# SonicVisualizer.net
KiCad netlist of a schematic drawn in EAGLE
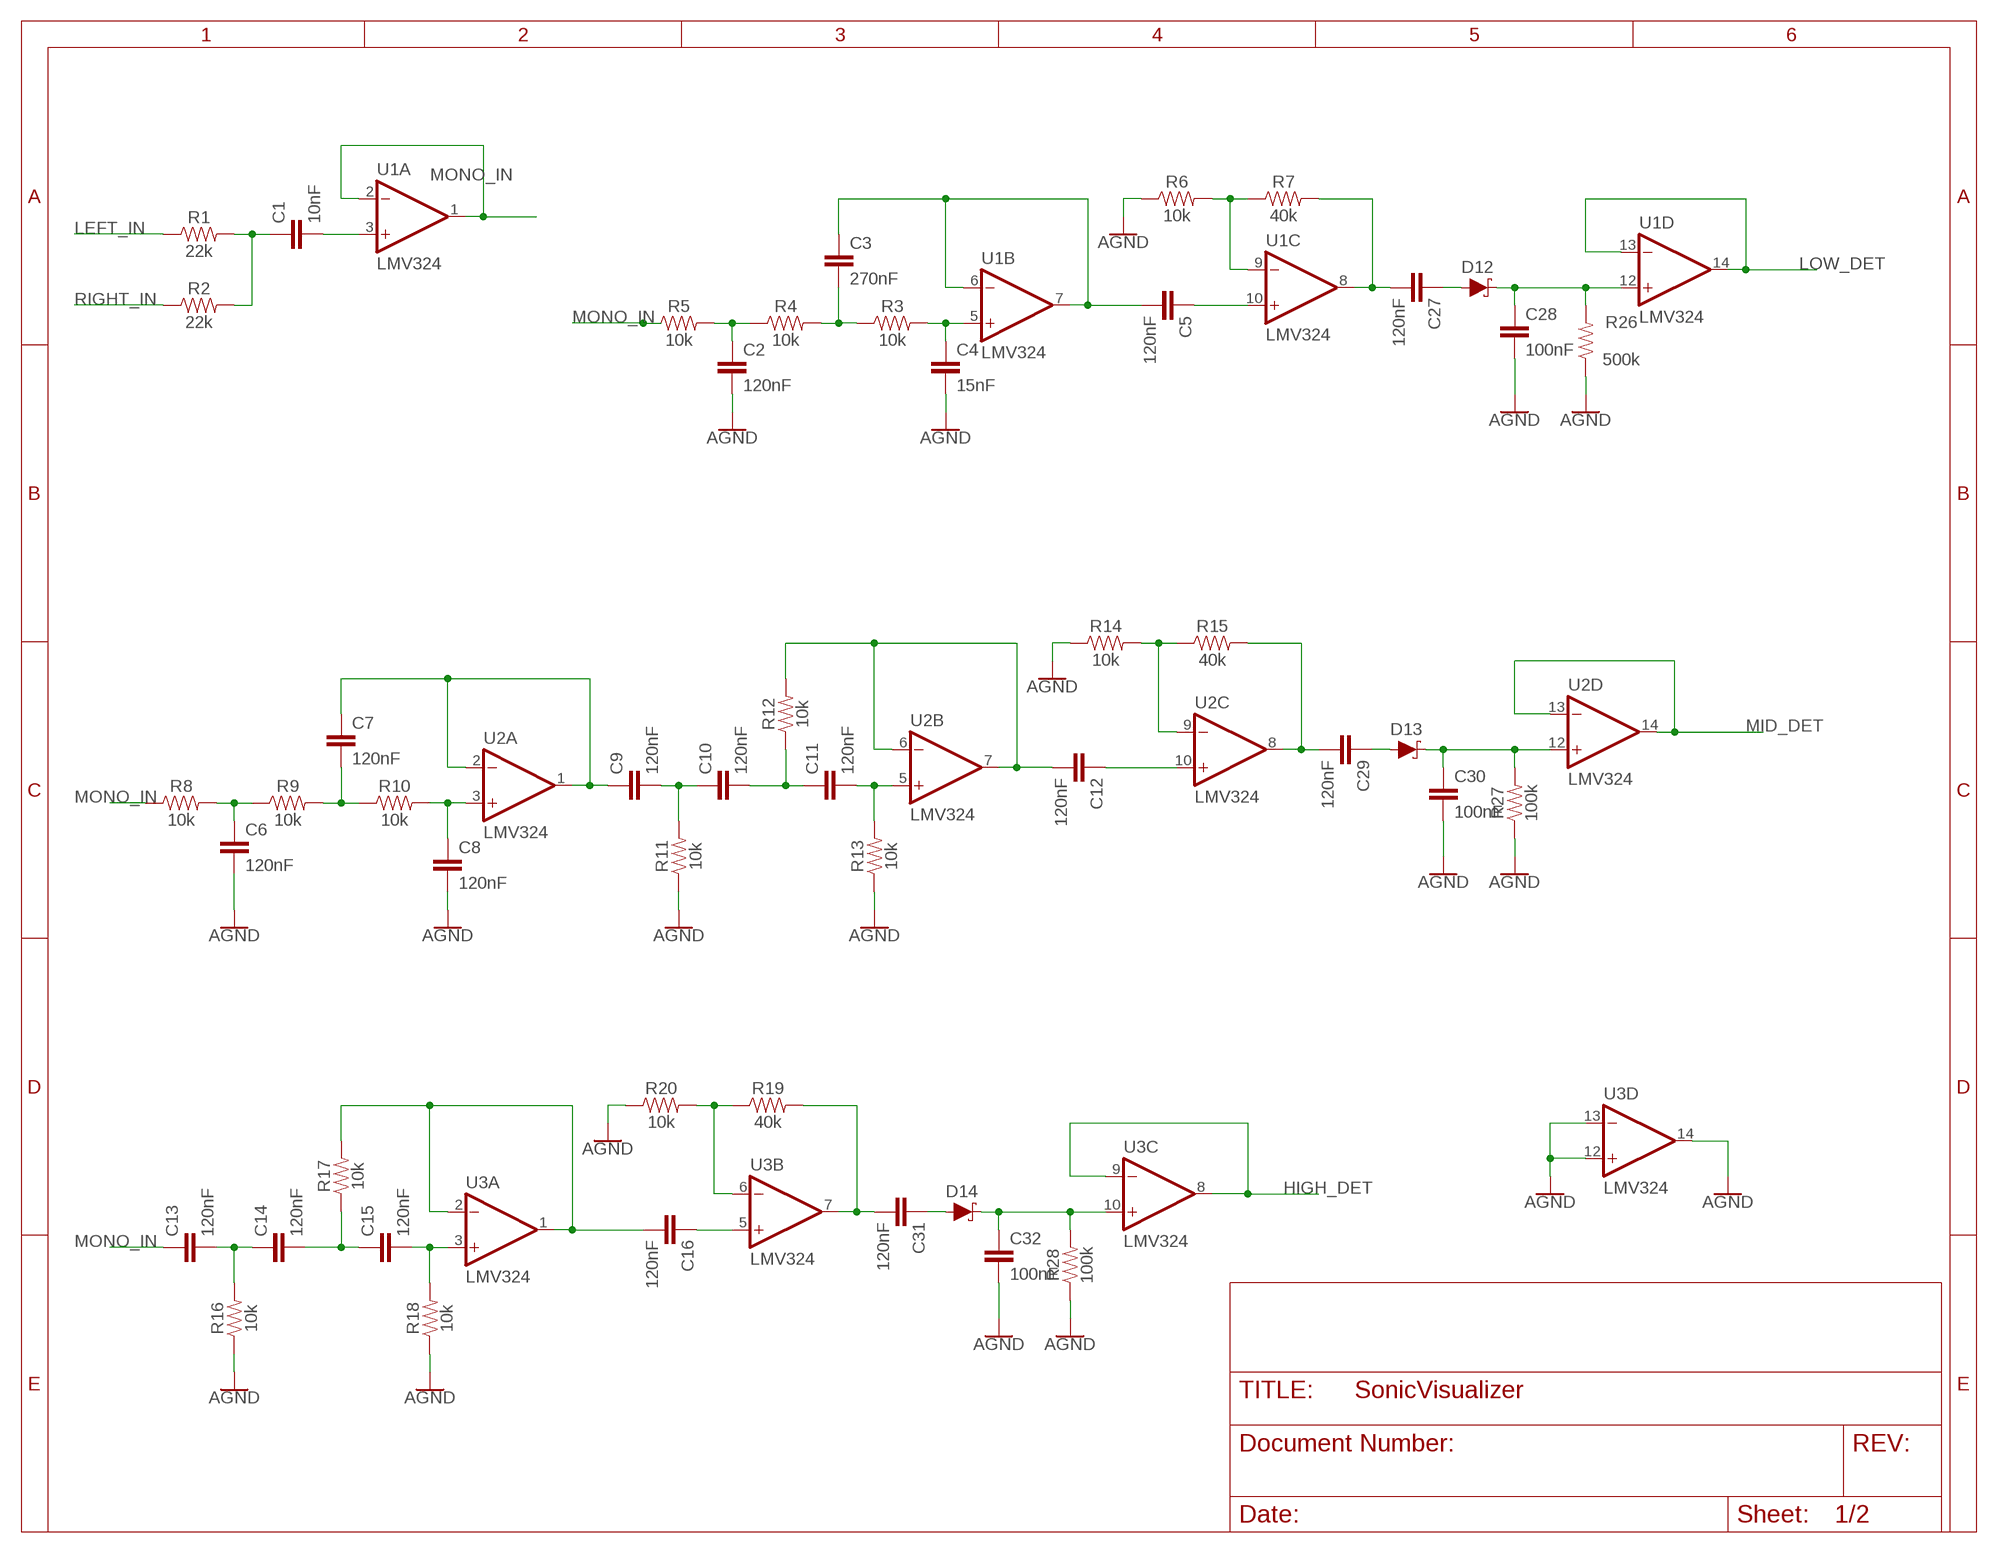
[diagram p0: schematic, sheet 1]
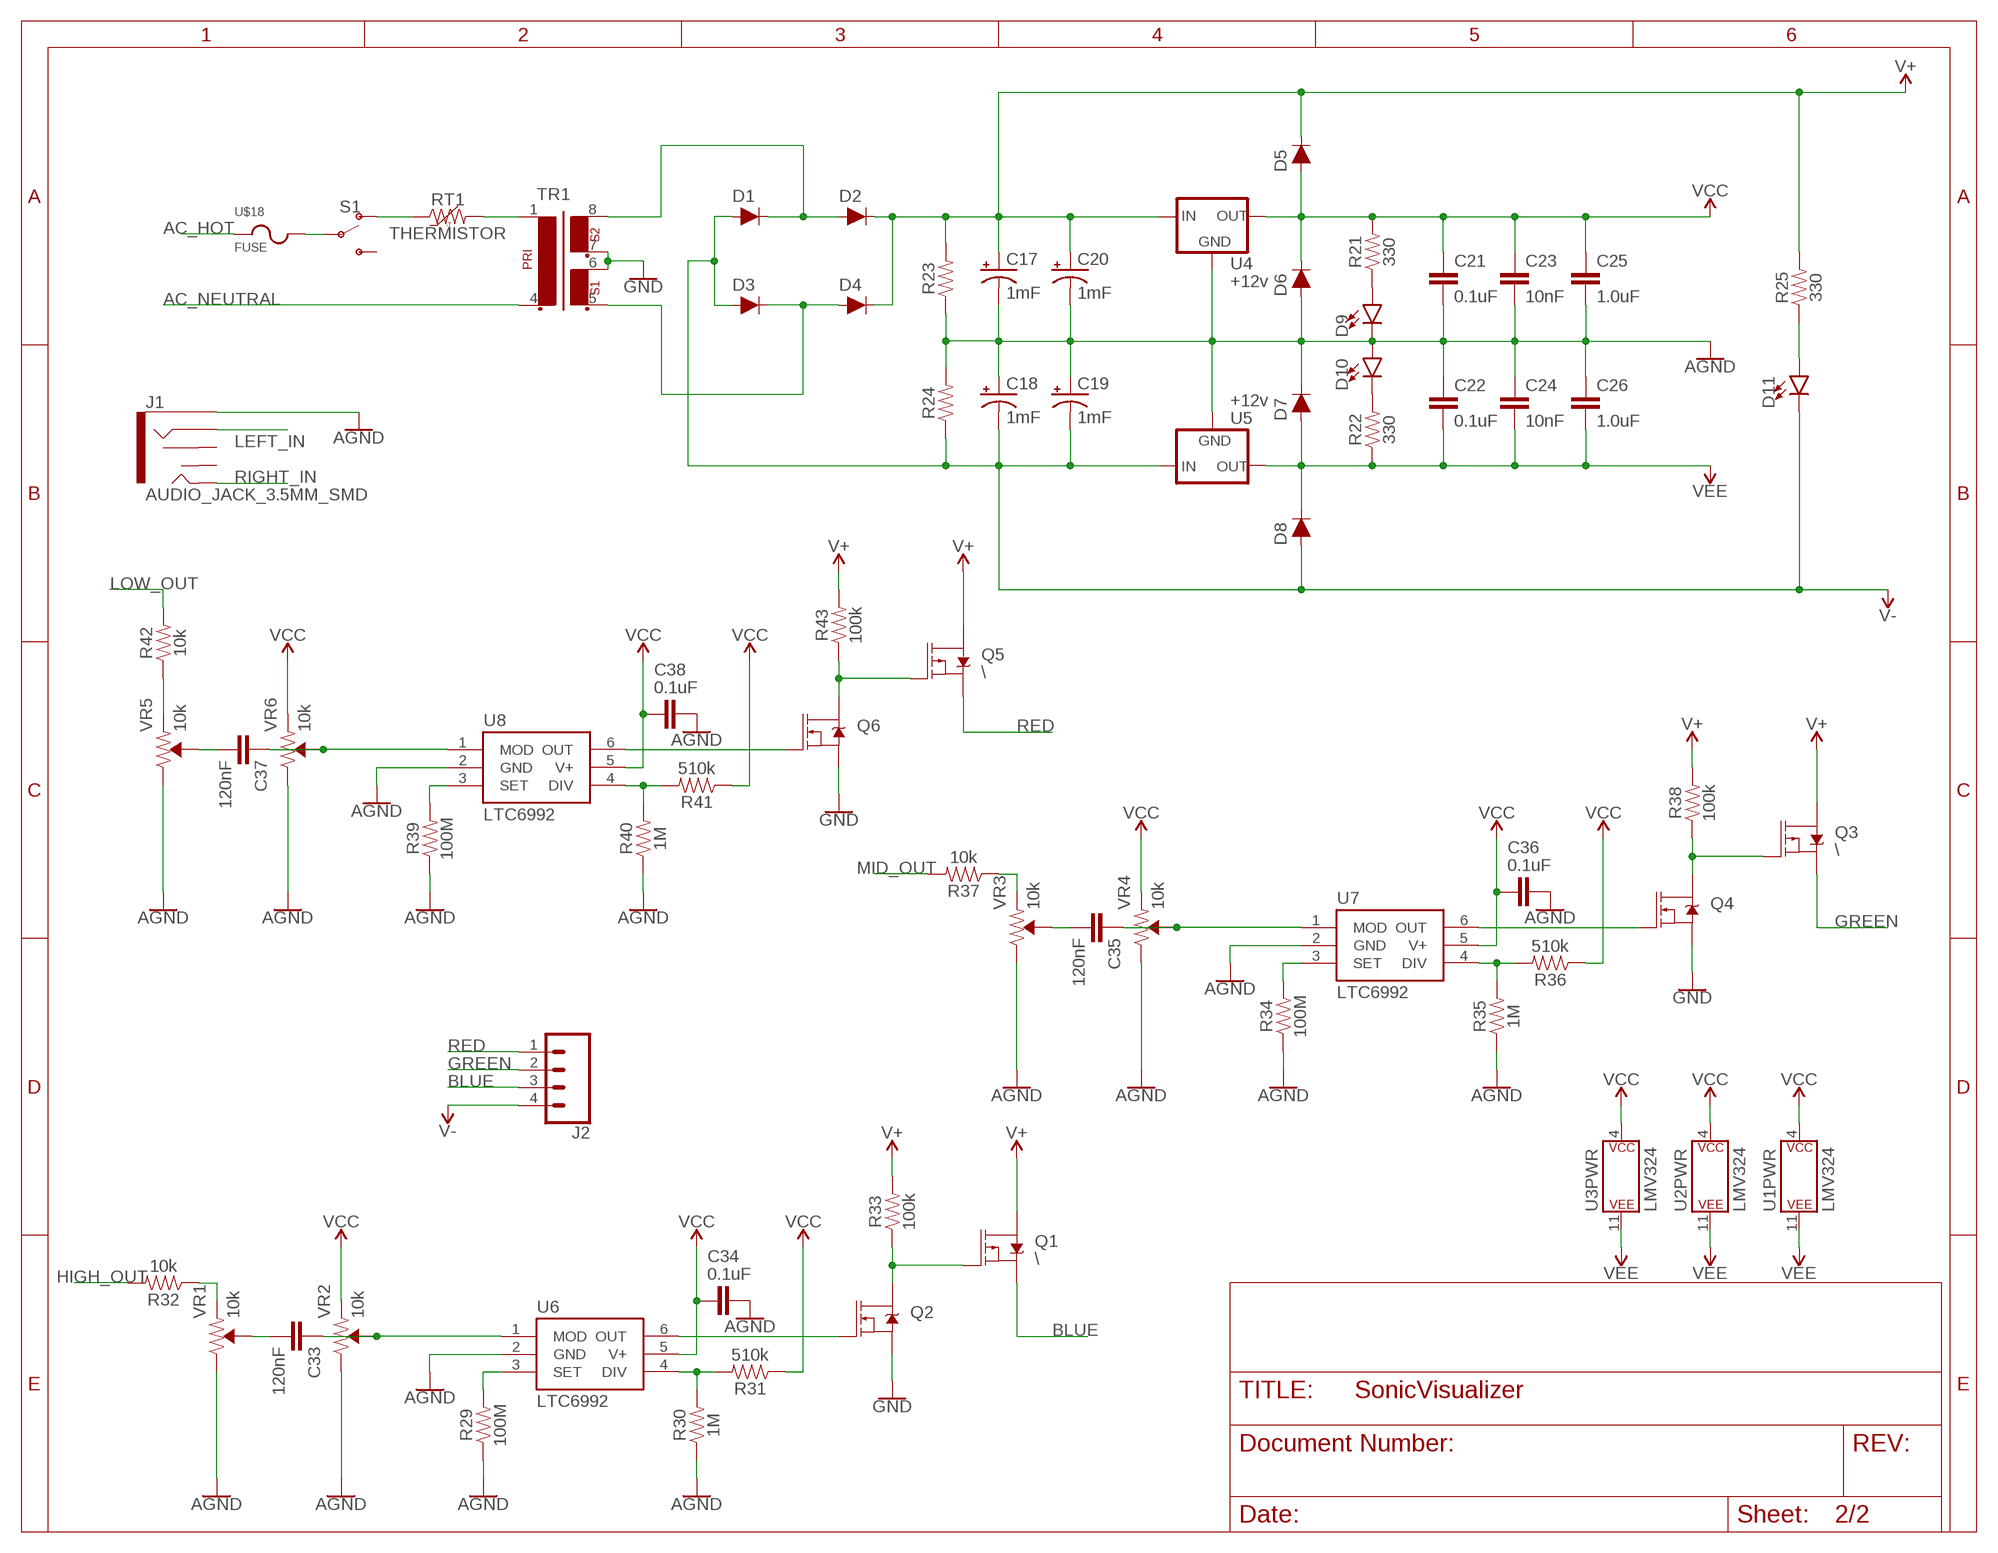
[diagram p1: schematic, sheet 2]

(export (version "E")
  (design (tool "Eeschema 10.0.6"))
  (components
    (comp (ref "C1")
      (value "10nF")
      (footprint "eagle-import:0603")
      (libsource (lib "eagle-import") (part "10NF-0603-50V-10%"))
    )
    (comp (ref "C2")
      (value "120nF")
      (footprint "eagle-import:0603")
      (libsource (lib "eagle-import") (part "0.1UF-0603-25V-(+80/-20%)"))
    )
    (comp (ref "C3")
      (value "270nF")
      (footprint "eagle-import:0603")
      (libsource (lib "eagle-import") (part "0.1UF-0603-25V-(+80/-20%)"))
    )
    (comp (ref "C4")
      (value "15nF")
      (footprint "eagle-import:0603")
      (libsource (lib "eagle-import") (part "0.1UF-0603-25V-(+80/-20%)"))
    )
    (comp (ref "C5")
      (value "120nF")
      (footprint "eagle-import:0603")
      (libsource (lib "eagle-import") (part "0.1UF-0603-25V-(+80/-20%)"))
    )
    (comp (ref "C6")
      (value "120nF")
      (footprint "eagle-import:0603")
      (libsource (lib "eagle-import") (part "0.1UF-0603-25V-(+80/-20%)"))
    )
    (comp (ref "C7")
      (value "120nF")
      (footprint "eagle-import:0603")
      (libsource (lib "eagle-import") (part "0.1UF-0603-25V-(+80/-20%)"))
    )
    (comp (ref "C8")
      (value "120nF")
      (footprint "eagle-import:0603")
      (libsource (lib "eagle-import") (part "0.1UF-0603-25V-(+80/-20%)"))
    )
    (comp (ref "C9")
      (value "120nF")
      (footprint "eagle-import:0603")
      (libsource (lib "eagle-import") (part "0.1UF-0603-25V-(+80/-20%)"))
    )
    (comp (ref "C10")
      (value "120nF")
      (footprint "eagle-import:0603")
      (libsource (lib "eagle-import") (part "0.1UF-0603-25V-(+80/-20%)"))
    )
    (comp (ref "C11")
      (value "120nF")
      (footprint "eagle-import:0603")
      (libsource (lib "eagle-import") (part "0.1UF-0603-25V-(+80/-20%)"))
    )
    (comp (ref "C12")
      (value "120nF")
      (footprint "eagle-import:0603")
      (libsource (lib "eagle-import") (part "0.1UF-0603-25V-(+80/-20%)"))
    )
    (comp (ref "C13")
      (value "120nF")
      (footprint "eagle-import:0603")
      (libsource (lib "eagle-import") (part "0.1UF-0603-25V-(+80/-20%)"))
    )
    (comp (ref "C14")
      (value "120nF")
      (footprint "eagle-import:0603")
      (libsource (lib "eagle-import") (part "0.1UF-0603-25V-(+80/-20%)"))
    )
    (comp (ref "C15")
      (value "120nF")
      (footprint "eagle-import:0603")
      (libsource (lib "eagle-import") (part "0.1UF-0603-25V-(+80/-20%)"))
    )
    (comp (ref "C16")
      (value "120nF")
      (footprint "eagle-import:0603")
      (libsource (lib "eagle-import") (part "0.1UF-0603-25V-(+80/-20%)"))
    )
    (comp (ref "C27")
      (value "120nF")
      (footprint "eagle-import:0603")
      (libsource (lib "eagle-import") (part "0.1UF-0603-25V-(+80/-20%)"))
    )
    (comp (ref "C28")
      (value "100nF")
      (footprint "eagle-import:0603")
      (libsource (lib "eagle-import") (part "0.1UF-0603-25V-(+80/-20%)"))
    )
    (comp (ref "C29")
      (value "120nF")
      (footprint "eagle-import:0603")
      (libsource (lib "eagle-import") (part "0.1UF-0603-25V-(+80/-20%)"))
    )
    (comp (ref "C30")
      (value "100nF")
      (footprint "eagle-import:0603")
      (libsource (lib "eagle-import") (part "0.1UF-0603-25V-(+80/-20%)"))
    )
    (comp (ref "C31")
      (value "120nF")
      (footprint "eagle-import:0603")
      (libsource (lib "eagle-import") (part "0.1UF-0603-25V-(+80/-20%)"))
    )
    (comp (ref "C32")
      (value "100nF")
      (footprint "eagle-import:0603")
      (libsource (lib "eagle-import") (part "0.1UF-0603-25V-(+80/-20%)"))
    )
    (comp (ref "D12")
      (value "DIODE-SCHOTTKY-SS14")
      (footprint "eagle-import:SMA-DIODE")
      (libsource (lib "eagle-import") (part "DIODE-SCHOTTKY-SS14"))
    )
    (comp (ref "D13")
      (value "DIODE-SCHOTTKY-SS14")
      (footprint "eagle-import:SMA-DIODE")
      (libsource (lib "eagle-import") (part "DIODE-SCHOTTKY-SS14"))
    )
    (comp (ref "D14")
      (value "DIODE-SCHOTTKY-SS14")
      (footprint "eagle-import:SMA-DIODE")
      (libsource (lib "eagle-import") (part "DIODE-SCHOTTKY-SS14"))
    )
    (comp (ref "R1")
      (value "22k")
      (footprint "eagle-import:0603")
      (libsource (lib "eagle-import") (part "22KOHM-0603-1/10W-1%"))
    )
    (comp (ref "R2")
      (value "22k")
      (footprint "eagle-import:0603")
      (libsource (lib "eagle-import") (part "22KOHM-0603-1/10W-1%"))
    )
    (comp (ref "R3")
      (value "10k")
      (footprint "eagle-import:0603")
      (libsource (lib "eagle-import") (part "10KOHM-0603-1/10W-1%"))
    )
    (comp (ref "R4")
      (value "10k")
      (footprint "eagle-import:0603")
      (libsource (lib "eagle-import") (part "10KOHM-0603-1/10W-1%"))
    )
    (comp (ref "R5")
      (value "10k")
      (footprint "eagle-import:0603")
      (libsource (lib "eagle-import") (part "10KOHM-0603-1/10W-1%"))
    )
    (comp (ref "R6")
      (value "10k")
      (footprint "eagle-import:0603")
      (libsource (lib "eagle-import") (part "10KOHM-0603-1/10W-1%"))
    )
    (comp (ref "R7")
      (value "40k")
      (footprint "eagle-import:0603")
      (libsource (lib "eagle-import") (part "10KOHM-0603-1/10W-1%"))
    )
    (comp (ref "R8")
      (value "10k")
      (footprint "eagle-import:0603")
      (libsource (lib "eagle-import") (part "10KOHM-0603-1/10W-1%"))
    )
    (comp (ref "R9")
      (value "10k")
      (footprint "eagle-import:0603")
      (libsource (lib "eagle-import") (part "10KOHM-0603-1/10W-1%"))
    )
    (comp (ref "R10")
      (value "10k")
      (footprint "eagle-import:0603")
      (libsource (lib "eagle-import") (part "10KOHM-0603-1/10W-1%"))
    )
    (comp (ref "R11")
      (value "10k")
      (footprint "eagle-import:0603")
      (libsource (lib "eagle-import") (part "10KOHM-0603-1/10W-1%"))
    )
    (comp (ref "R12")
      (value "10k")
      (footprint "eagle-import:0603")
      (libsource (lib "eagle-import") (part "10KOHM-0603-1/10W-1%"))
    )
    (comp (ref "R13")
      (value "10k")
      (footprint "eagle-import:0603")
      (libsource (lib "eagle-import") (part "10KOHM-0603-1/10W-1%"))
    )
    (comp (ref "R14")
      (value "10k")
      (footprint "eagle-import:0603")
      (libsource (lib "eagle-import") (part "10KOHM-0603-1/10W-1%"))
    )
    (comp (ref "R15")
      (value "40k")
      (footprint "eagle-import:0603")
      (libsource (lib "eagle-import") (part "10KOHM-0603-1/10W-1%"))
    )
    (comp (ref "R16")
      (value "10k")
      (footprint "eagle-import:0603")
      (libsource (lib "eagle-import") (part "10KOHM-0603-1/10W-1%"))
    )
    (comp (ref "R17")
      (value "10k")
      (footprint "eagle-import:0603")
      (libsource (lib "eagle-import") (part "10KOHM-0603-1/10W-1%"))
    )
    (comp (ref "R18")
      (value "10k")
      (footprint "eagle-import:0603")
      (libsource (lib "eagle-import") (part "10KOHM-0603-1/10W-1%"))
    )
    (comp (ref "R19")
      (value "40k")
      (footprint "eagle-import:0603")
      (libsource (lib "eagle-import") (part "10KOHM-0603-1/10W-1%"))
    )
    (comp (ref "R20")
      (value "10k")
      (footprint "eagle-import:0603")
      (libsource (lib "eagle-import") (part "10KOHM-0603-1/10W-1%"))
    )
    (comp (ref "R26")
      (value "500k")
      (footprint "eagle-import:0603")
      (libsource (lib "eagle-import") (part "10KOHM-0603-1/10W-1%"))
    )
    (comp (ref "R27")
      (value "100k")
      (footprint "eagle-import:0603")
      (libsource (lib "eagle-import") (part "10KOHM-0603-1/10W-1%"))
    )
    (comp (ref "R28")
      (value "100k")
      (footprint "eagle-import:0603")
      (libsource (lib "eagle-import") (part "10KOHM-0603-1/10W-1%"))
    )
    (comp (ref "U1")
      (value "LMV324")
      (footprint "eagle-import:SO14")
      (libsource (lib "eagle-import") (part "LMV324"))
    )
    (comp (ref "U2")
      (value "LMV324")
      (footprint "eagle-import:SO14")
      (libsource (lib "eagle-import") (part "LMV324"))
    )
    (comp (ref "U3")
      (value "LMV324")
      (footprint "eagle-import:SO14")
      (libsource (lib "eagle-import") (part "LMV324"))
    )
    (comp (ref "C17")
      (value "1mF")
      (footprint "eagle-import:CPOL-RADIAL-5MM-10MM")
      (libsource (lib "eagle-import") (part "1000UF-RADIAL-5MM-25V-20%"))
    )
    (comp (ref "C18")
      (value "1mF")
      (footprint "eagle-import:CPOL-RADIAL-5MM-10MM")
      (libsource (lib "eagle-import") (part "1000UF-RADIAL-5MM-25V-20%"))
    )
    (comp (ref "C19")
      (value "1mF")
      (footprint "eagle-import:CPOL-RADIAL-5MM-10MM")
      (libsource (lib "eagle-import") (part "1000UF-RADIAL-5MM-25V-20%"))
    )
    (comp (ref "C20")
      (value "1mF")
      (footprint "eagle-import:CPOL-RADIAL-5MM-10MM")
      (libsource (lib "eagle-import") (part "1000UF-RADIAL-5MM-25V-20%"))
    )
    (comp (ref "C21")
      (value "0.1uF")
      (footprint "eagle-import:0603")
      (libsource (lib "eagle-import") (part "0.1UF-0603-25V-(+80/-20%)"))
    )
    (comp (ref "C22")
      (value "0.1uF")
      (footprint "eagle-import:0603")
      (libsource (lib "eagle-import") (part "0.1UF-0603-25V-(+80/-20%)"))
    )
    (comp (ref "C23")
      (value "10nF")
      (footprint "eagle-import:0603")
      (libsource (lib "eagle-import") (part "10NF-0603-50V-10%"))
    )
    (comp (ref "C24")
      (value "10nF")
      (footprint "eagle-import:0603")
      (libsource (lib "eagle-import") (part "10NF-0603-50V-10%"))
    )
    (comp (ref "C25")
      (value "1.0uF")
      (footprint "eagle-import:0603")
      (libsource (lib "eagle-import") (part "1.0UF-0603-16V-10%"))
    )
    (comp (ref "C26")
      (value "1.0uF")
      (footprint "eagle-import:0603")
      (libsource (lib "eagle-import") (part "1.0UF-0603-16V-10%"))
    )
    (comp (ref "C33")
      (value "120nF")
      (footprint "eagle-import:0603")
      (libsource (lib "eagle-import") (part "0.1UF-0603-25V-(+80/-20%)"))
    )
    (comp (ref "C34")
      (value "0.1uF")
      (footprint "eagle-import:0603")
      (libsource (lib "eagle-import") (part "0.1UF-0603-25V-(+80/-20%)"))
    )
    (comp (ref "C35")
      (value "120nF")
      (footprint "eagle-import:0603")
      (libsource (lib "eagle-import") (part "0.1UF-0603-25V-(+80/-20%)"))
    )
    (comp (ref "C36")
      (value "0.1uF")
      (footprint "eagle-import:0603")
      (libsource (lib "eagle-import") (part "0.1UF-0603-25V-(+80/-20%)"))
    )
    (comp (ref "C37")
      (value "120nF")
      (footprint "eagle-import:0603")
      (libsource (lib "eagle-import") (part "0.1UF-0603-25V-(+80/-20%)"))
    )
    (comp (ref "C38")
      (value "0.1uF")
      (footprint "eagle-import:0603")
      (libsource (lib "eagle-import") (part "0.1UF-0603-25V-(+80/-20%)"))
    )
    (comp (ref "D1")
      (value "DIODE-PTH")
      (footprint "eagle-import:DIODE-1N4001")
      (libsource (lib "eagle-import") (part "DIODE-PTH"))
    )
    (comp (ref "D2")
      (value "DIODE-PTH")
      (footprint "eagle-import:DIODE-1N4001")
      (libsource (lib "eagle-import") (part "DIODE-PTH"))
    )
    (comp (ref "D3")
      (value "DIODE-PTH")
      (footprint "eagle-import:DIODE-1N4001")
      (libsource (lib "eagle-import") (part "DIODE-PTH"))
    )
    (comp (ref "D4")
      (value "DIODE-PTH")
      (footprint "eagle-import:DIODE-1N4001")
      (libsource (lib "eagle-import") (part "DIODE-PTH"))
    )
    (comp (ref "D5")
      (value "DIODE-PTH")
      (footprint "eagle-import:DIODE-1N4001")
      (libsource (lib "eagle-import") (part "DIODE-PTH"))
    )
    (comp (ref "D6")
      (value "DIODE-PTH")
      (footprint "eagle-import:DIODE-1N4001")
      (libsource (lib "eagle-import") (part "DIODE-PTH"))
    )
    (comp (ref "D7")
      (value "DIODE-PTH")
      (footprint "eagle-import:DIODE-1N4001")
      (libsource (lib "eagle-import") (part "DIODE-PTH"))
    )
    (comp (ref "D8")
      (value "DIODE-PTH")
      (footprint "eagle-import:DIODE-1N4001")
      (libsource (lib "eagle-import") (part "DIODE-PTH"))
    )
    (comp (ref "D9")
      (value "LED0603")
      (footprint "eagle-import:LED-0603")
      (libsource (lib "eagle-import") (part "LED0603"))
    )
    (comp (ref "D10")
      (value "LED0603")
      (footprint "eagle-import:LED-0603")
      (libsource (lib "eagle-import") (part "LED0603"))
    )
    (comp (ref "D11")
      (value "LED0603")
      (footprint "eagle-import:LED-0603")
      (libsource (lib "eagle-import") (part "LED0603"))
    )
    (comp (ref "J1")
      (value "AUDIO_JACK_3.5MM_SMD")
      (footprint "eagle-import:AUDIO-JACK-3.5MM-SMD")
      (libsource (lib "eagle-import") (part "AUDIO_JACK_3.5MM_SMD"))
    )
    (comp (ref "J2")
      (value "CONN_04")
      (footprint "eagle-import:1X04")
      (libsource (lib "eagle-import") (part "CONN_04"))
    )
    (comp (ref "Q1")
      (value "\\")
      (footprint "eagle-import:SOT23-3")
      (libsource (lib "eagle-import") (part "MOSFET_PCH-IRLML2244"))
    )
    (comp (ref "Q2")
      (value "MOSFET-NCH-2N7002PW")
      (footprint "eagle-import:SOT323")
      (libsource (lib "eagle-import") (part "MOSFET-NCH-2N7002PW"))
    )
    (comp (ref "Q3")
      (value "\\")
      (footprint "eagle-import:SOT23-3")
      (libsource (lib "eagle-import") (part "MOSFET_PCH-IRLML2244"))
    )
    (comp (ref "Q4")
      (value "MOSFET-NCH-2N7002PW")
      (footprint "eagle-import:SOT323")
      (libsource (lib "eagle-import") (part "MOSFET-NCH-2N7002PW"))
    )
    (comp (ref "Q5")
      (value "\\")
      (footprint "eagle-import:SOT23-3")
      (libsource (lib "eagle-import") (part "MOSFET_PCH-IRLML2244"))
    )
    (comp (ref "Q6")
      (value "MOSFET-NCH-2N7002PW")
      (footprint "eagle-import:SOT323")
      (libsource (lib "eagle-import") (part "MOSFET-NCH-2N7002PW"))
    )
    (comp (ref "R21")
      (value "330")
      (footprint "eagle-import:0603")
      (libsource (lib "eagle-import") (part "330OHM-0603-1/10W-1%"))
    )
    (comp (ref "R22")
      (value "330")
      (footprint "eagle-import:0603")
      (libsource (lib "eagle-import") (part "330OHM-0603-1/10W-1%"))
    )
    (comp (ref "R23")
      (value "RESISTORAXIAL-0.3")
      (footprint "eagle-import:AXIAL-0.3")
      (libsource (lib "eagle-import") (part "RESISTORAXIAL-0.3"))
    )
    (comp (ref "R24")
      (value "RESISTORAXIAL-0.3")
      (footprint "eagle-import:AXIAL-0.3")
      (libsource (lib "eagle-import") (part "RESISTORAXIAL-0.3"))
    )
    (comp (ref "R25")
      (value "330")
      (footprint "eagle-import:0603")
      (libsource (lib "eagle-import") (part "330OHM-0603-1/10W-1%"))
    )
    (comp (ref "R29")
      (value "100M")
      (footprint "eagle-import:0603")
      (libsource (lib "eagle-import") (part "10KOHM-0603-1/10W-1%"))
    )
    (comp (ref "R30")
      (value "1M")
      (footprint "eagle-import:0603")
      (libsource (lib "eagle-import") (part "10KOHM-0603-1/10W-1%"))
    )
    (comp (ref "R31")
      (value "510k")
      (footprint "eagle-import:0603")
      (libsource (lib "eagle-import") (part "10KOHM-0603-1/10W-1%"))
    )
    (comp (ref "R32")
      (value "10k")
      (footprint "eagle-import:0603")
      (libsource (lib "eagle-import") (part "10KOHM-0603-1/10W-1%"))
    )
    (comp (ref "R33")
      (value "100k")
      (footprint "eagle-import:0603")
      (libsource (lib "eagle-import") (part "10KOHM-0603-1/10W-1%"))
    )
    (comp (ref "R34")
      (value "100M")
      (footprint "eagle-import:0603")
      (libsource (lib "eagle-import") (part "10KOHM-0603-1/10W-1%"))
    )
    (comp (ref "R35")
      (value "1M")
      (footprint "eagle-import:0603")
      (libsource (lib "eagle-import") (part "10KOHM-0603-1/10W-1%"))
    )
    (comp (ref "R36")
      (value "510k")
      (footprint "eagle-import:0603")
      (libsource (lib "eagle-import") (part "10KOHM-0603-1/10W-1%"))
    )
    (comp (ref "R37")
      (value "10k")
      (footprint "eagle-import:0603")
      (libsource (lib "eagle-import") (part "10KOHM-0603-1/10W-1%"))
    )
    (comp (ref "R38")
      (value "100k")
      (footprint "eagle-import:0603")
      (libsource (lib "eagle-import") (part "10KOHM-0603-1/10W-1%"))
    )
    (comp (ref "R39")
      (value "100M")
      (footprint "eagle-import:0603")
      (libsource (lib "eagle-import") (part "10KOHM-0603-1/10W-1%"))
    )
    (comp (ref "R40")
      (value "1M")
      (footprint "eagle-import:0603")
      (libsource (lib "eagle-import") (part "10KOHM-0603-1/10W-1%"))
    )
    (comp (ref "R41")
      (value "510k")
      (footprint "eagle-import:0603")
      (libsource (lib "eagle-import") (part "10KOHM-0603-1/10W-1%"))
    )
    (comp (ref "R42")
      (value "10k")
      (footprint "eagle-import:0603")
      (libsource (lib "eagle-import") (part "10KOHM-0603-1/10W-1%"))
    )
    (comp (ref "R43")
      (value "100k")
      (footprint "eagle-import:0603")
      (libsource (lib "eagle-import") (part "10KOHM-0603-1/10W-1%"))
    )
    (comp (ref "RT1")
      (value "THERMISTOR")
      (footprint "eagle-import:THERMISTOR")
      (libsource (lib "eagle-import") (part "THERMISTOR"))
    )
    (comp (ref "S1")
      (value "SWITCH-SPDT-PTH-11.6X4.0MM")
      (footprint "eagle-import:SWITCH_SPDT_PTH_11.6X4.0MM")
      (libsource (lib "eagle-import") (part "SWITCH-SPDT-PTH-11.6X4.0MM"))
    )
    (comp (ref "TR1")
      (value "EE20-2")
      (footprint "eagle-import:EE20-2")
      (libsource (lib "eagle-import") (part "EE20-2"))
    )
    (comp (ref "U$18")
      (value "FUSE")
      (footprint "eagle-import:THERMISTOR")
      (libsource (lib "eagle-import") (part "FUSE"))
    )
    (comp (ref "U4")
      (value "+12v")
      (footprint "eagle-import:TO-252")
      (libsource (lib "eagle-import") (part "V_REG_78XX7812"))
    )
    (comp (ref "U5")
      (value "+12v")
      (footprint "eagle-import:TO-252")
      (libsource (lib "eagle-import") (part "V_REG_78XX7812"))
    )
    (comp (ref "U6")
      (value "LTC6992")
      (footprint "eagle-import:SOP06")
      (libsource (lib "eagle-import") (part "LTC6992"))
    )
    (comp (ref "U7")
      (value "LTC6992")
      (footprint "eagle-import:SOP06")
      (libsource (lib "eagle-import") (part "LTC6992"))
    )
    (comp (ref "U8")
      (value "LTC6992")
      (footprint "eagle-import:SOP06")
      (libsource (lib "eagle-import") (part "LTC6992"))
    )
    (comp (ref "VR1")
      (value "10k")
      (footprint "eagle-import:TRIMPOT-SMD-3MM-CLOSED")
      (libsource (lib "eagle-import") (part "TRIMPOT-SMD-3MM-CLOSED-1/8W-20%"))
    )
    (comp (ref "VR2")
      (value "10k")
      (footprint "eagle-import:TRIMPOT-SMD-3MM-CLOSED")
      (libsource (lib "eagle-import") (part "TRIMPOT-SMD-3MM-CLOSED-1/8W-20%"))
    )
    (comp (ref "VR3")
      (value "10k")
      (footprint "eagle-import:TRIMPOT-SMD-3MM-CLOSED")
      (libsource (lib "eagle-import") (part "TRIMPOT-SMD-3MM-CLOSED-1/8W-20%"))
    )
    (comp (ref "VR4")
      (value "10k")
      (footprint "eagle-import:TRIMPOT-SMD-3MM-CLOSED")
      (libsource (lib "eagle-import") (part "TRIMPOT-SMD-3MM-CLOSED-1/8W-20%"))
    )
    (comp (ref "VR5")
      (value "10k")
      (footprint "eagle-import:TRIMPOT-SMD-3MM-CLOSED")
      (libsource (lib "eagle-import") (part "TRIMPOT-SMD-3MM-CLOSED-1/8W-20%"))
    )
    (comp (ref "VR6")
      (value "10k")
      (footprint "eagle-import:TRIMPOT-SMD-3MM-CLOSED")
      (libsource (lib "eagle-import") (part "TRIMPOT-SMD-3MM-CLOSED-1/8W-20%"))
    )
  )
  (nets
    (net (code "1") (name "AC_HOT") (class "Default")
      (node (ref "U$18") (pin "1") (pinfunction "P$1_1") (pintype "bidirectional"))
    )
    (net (code "2") (name "AC_NEUTRAL") (class "Default")
      (node (ref "TR1") (pin "4") (pinfunction "2_4") (pintype "passive"))
    )
    (net (code "3") (name "AGND") (class "Default")
      (node (ref "C17") (pin "-") (pinfunction "-_-") (pintype "passive"))
      (node (ref "C18") (pin "+") (pinfunction "+_+") (pintype "passive"))
      (node (ref "C19") (pin "+") (pinfunction "+_+") (pintype "passive"))
      (node (ref "C2") (pin "2") (pinfunction "2_2") (pintype "passive"))
      (node (ref "C20") (pin "-") (pinfunction "-_-") (pintype "passive"))
      (node (ref "C21") (pin "2") (pinfunction "2_2") (pintype "passive"))
      (node (ref "C22") (pin "1") (pinfunction "1_1") (pintype "passive"))
      (node (ref "C23") (pin "2") (pinfunction "2_2") (pintype "passive"))
      (node (ref "C24") (pin "1") (pinfunction "1_1") (pintype "passive"))
      (node (ref "C25") (pin "2") (pinfunction "2_2") (pintype "passive"))
      (node (ref "C26") (pin "1") (pinfunction "1_1") (pintype "passive"))
      (node (ref "C28") (pin "2") (pinfunction "2_2") (pintype "passive"))
      (node (ref "C30") (pin "2") (pinfunction "2_2") (pintype "passive"))
      (node (ref "C32") (pin "2") (pinfunction "2_2") (pintype "passive"))
      (node (ref "C34") (pin "2") (pinfunction "2_2") (pintype "passive"))
      (node (ref "C36") (pin "2") (pinfunction "2_2") (pintype "passive"))
      (node (ref "C38") (pin "2") (pinfunction "2_2") (pintype "passive"))
      (node (ref "C4") (pin "2") (pinfunction "2_2") (pintype "passive"))
      (node (ref "C6") (pin "2") (pinfunction "2_2") (pintype "passive"))
      (node (ref "C8") (pin "2") (pinfunction "2_2") (pintype "passive"))
      (node (ref "D10") (pin "A") (pinfunction "A_A") (pintype "passive"))
      (node (ref "D6") (pin "A") (pinfunction "A_A") (pintype "passive"))
      (node (ref "D7") (pin "C") (pinfunction "C_C") (pintype "passive"))
      (node (ref "D9") (pin "C") (pinfunction "C_C") (pintype "passive"))
      (node (ref "J1") (pin "SLEEVE") (pinfunction "SLEEVE_SLEEVE") (pintype "bidirectional"))
      (node (ref "R11") (pin "1") (pinfunction "1_1") (pintype "passive"))
      (node (ref "R13") (pin "1") (pinfunction "1_1") (pintype "passive"))
      (node (ref "R14") (pin "1") (pinfunction "1_1") (pintype "passive"))
      (node (ref "R16") (pin "1") (pinfunction "1_1") (pintype "passive"))
      (node (ref "R18") (pin "1") (pinfunction "1_1") (pintype "passive"))
      (node (ref "R20") (pin "1") (pinfunction "1_1") (pintype "passive"))
      (node (ref "R23") (pin "P$1") (pinfunction "1_P$1") (pintype "passive"))
      (node (ref "R24") (pin "P$2") (pinfunction "2_P$2") (pintype "passive"))
      (node (ref "R26") (pin "1") (pinfunction "1_1") (pintype "passive"))
      (node (ref "R27") (pin "1") (pinfunction "1_1") (pintype "passive"))
      (node (ref "R28") (pin "1") (pinfunction "1_1") (pintype "passive"))
      (node (ref "R29") (pin "1") (pinfunction "1_1") (pintype "passive"))
      (node (ref "R30") (pin "1") (pinfunction "1_1") (pintype "passive"))
      (node (ref "R34") (pin "1") (pinfunction "1_1") (pintype "passive"))
      (node (ref "R35") (pin "1") (pinfunction "1_1") (pintype "passive"))
      (node (ref "R39") (pin "1") (pinfunction "1_1") (pintype "passive"))
      (node (ref "R40") (pin "1") (pinfunction "1_1") (pintype "passive"))
      (node (ref "R6") (pin "1") (pinfunction "1_1") (pintype "passive"))
      (node (ref "U3") (pin "12") (pinfunction "+IN_12") (pintype "input"))
      (node (ref "U3") (pin "13") (pinfunction "-IN_13") (pintype "input"))
      (node (ref "U3") (pin "14") (pinfunction "OUT_14") (pintype "output"))
      (node (ref "U4") (pin "3") (pinfunction "GND_3") (pintype "input"))
      (node (ref "U5") (pin "3") (pinfunction "GND_3") (pintype "input"))
      (node (ref "U6") (pin "2") (pinfunction "GND_2") (pintype "power_in"))
      (node (ref "U7") (pin "2") (pinfunction "GND_2") (pintype "power_in"))
      (node (ref "U8") (pin "2") (pinfunction "GND_2") (pintype "power_in"))
      (node (ref "VR1") (pin "3") (pinfunction "CW_3") (pintype "passive"))
      (node (ref "VR2") (pin "3") (pinfunction "CW_3") (pintype "passive"))
      (node (ref "VR3") (pin "3") (pinfunction "CW_3") (pintype "passive"))
      (node (ref "VR4") (pin "3") (pinfunction "CW_3") (pintype "passive"))
      (node (ref "VR5") (pin "3") (pinfunction "CW_3") (pintype "passive"))
      (node (ref "VR6") (pin "3") (pinfunction "CW_3") (pintype "passive"))
    )
    (net (code "4") (name "BLUE") (class "Default")
      (node (ref "J2") (pin "3") (pinfunction "3_3") (pintype "passive"))
      (node (ref "Q1") (pin "2") (pinfunction "S_2") (pintype "bidirectional"))
    )
    (net (code "5") (name "GND") (class "Default")
      (node (ref "Q2") (pin "2") (pinfunction "S_2") (pintype "bidirectional"))
      (node (ref "Q4") (pin "2") (pinfunction "S_2") (pintype "bidirectional"))
      (node (ref "Q6") (pin "2") (pinfunction "S_2") (pintype "bidirectional"))
      (node (ref "TR1") (pin "6") (pinfunction "4_6") (pintype "passive"))
      (node (ref "TR1") (pin "7") (pinfunction "5_7") (pintype "passive"))
    )
    (net (code "6") (name "GREEN") (class "Default")
      (node (ref "J2") (pin "2") (pinfunction "2_2") (pintype "passive"))
      (node (ref "Q3") (pin "2") (pinfunction "S_2") (pintype "bidirectional"))
    )
    (net (code "7") (name "HIGH_DET") (class "Default")
      (node (ref "U3") (pin "8") (pinfunction "OUT_8") (pintype "output"))
      (node (ref "U3") (pin "9") (pinfunction "-IN_9") (pintype "input"))
    )
    (net (code "8") (name "HIGH_OUT") (class "Default")
      (node (ref "R32") (pin "2") (pinfunction "2_2") (pintype "passive"))
    )
    (net (code "9") (name "LEFT_IN") (class "Default")
      (node (ref "J1") (pin "RING") (pinfunction "RING_RING") (pintype "bidirectional"))
      (node (ref "R1") (pin "1") (pinfunction "1_1") (pintype "passive"))
    )
    (net (code "10") (name "LOW_DET") (class "Default")
      (node (ref "U1") (pin "13") (pinfunction "-IN_13") (pintype "input"))
      (node (ref "U1") (pin "14") (pinfunction "OUT_14") (pintype "output"))
    )
    (net (code "11") (name "LOW_OUT") (class "Default")
      (node (ref "R42") (pin "2") (pinfunction "2_2") (pintype "passive"))
    )
    (net (code "12") (name "MID_DET") (class "Default")
      (node (ref "U2") (pin "13") (pinfunction "-IN_13") (pintype "input"))
      (node (ref "U2") (pin "14") (pinfunction "OUT_14") (pintype "output"))
    )
    (net (code "13") (name "MID_OUT") (class "Default")
      (node (ref "R37") (pin "2") (pinfunction "2_2") (pintype "passive"))
    )
    (net (code "14") (name "MONO_IN") (class "Default")
      (node (ref "C13") (pin "1") (pinfunction "1_1") (pintype "passive"))
      (node (ref "R5") (pin "1") (pinfunction "1_1") (pintype "passive"))
      (node (ref "R8") (pin "1") (pinfunction "1_1") (pintype "passive"))
      (node (ref "U1") (pin "1") (pinfunction "OUT_1") (pintype "output"))
      (node (ref "U1") (pin "2") (pinfunction "-IN_2") (pintype "input"))
    )
    (net (code "15") (name "Net-(C1-Pad1)") (class "Default")
      (node (ref "C1") (pin "1") (pinfunction "1_1") (pintype "passive"))
      (node (ref "R1") (pin "2") (pinfunction "2_2") (pintype "passive"))
      (node (ref "R2") (pin "2") (pinfunction "2_2") (pintype "passive"))
    )
    (net (code "16") (name "Net-(C2-Pad1)") (class "Default")
      (node (ref "C2") (pin "1") (pinfunction "1_1") (pintype "passive"))
      (node (ref "R4") (pin "1") (pinfunction "1_1") (pintype "passive"))
      (node (ref "R5") (pin "2") (pinfunction "2_2") (pintype "passive"))
    )
    (net (code "17") (name "Net-(C3-Pad2)") (class "Default")
      (node (ref "C3") (pin "2") (pinfunction "2_2") (pintype "passive"))
      (node (ref "R3") (pin "1") (pinfunction "1_1") (pintype "passive"))
      (node (ref "R4") (pin "2") (pinfunction "2_2") (pintype "passive"))
    )
    (net (code "18") (name "Net-(C6-Pad1)") (class "Default")
      (node (ref "C6") (pin "1") (pinfunction "1_1") (pintype "passive"))
      (node (ref "R8") (pin "2") (pinfunction "2_2") (pintype "passive"))
      (node (ref "R9") (pin "1") (pinfunction "1_1") (pintype "passive"))
    )
    (net (code "19") (name "Net-(C7-Pad2)") (class "Default")
      (node (ref "C7") (pin "2") (pinfunction "2_2") (pintype "passive"))
      (node (ref "R10") (pin "1") (pinfunction "1_1") (pintype "passive"))
      (node (ref "R9") (pin "2") (pinfunction "2_2") (pintype "passive"))
    )
    (net (code "20") (name "Net-(C10-Pad1)") (class "Default")
      (node (ref "C10") (pin "1") (pinfunction "1_1") (pintype "passive"))
      (node (ref "C9") (pin "2") (pinfunction "2_2") (pintype "passive"))
      (node (ref "R11") (pin "2") (pinfunction "2_2") (pintype "passive"))
    )
    (net (code "21") (name "Net-(C10-Pad2)") (class "Default")
      (node (ref "C10") (pin "2") (pinfunction "2_2") (pintype "passive"))
      (node (ref "C11") (pin "1") (pinfunction "1_1") (pintype "passive"))
      (node (ref "R12") (pin "1") (pinfunction "1_1") (pintype "passive"))
    )
    (net (code "22") (name "Net-(C13-Pad2)") (class "Default")
      (node (ref "C13") (pin "2") (pinfunction "2_2") (pintype "passive"))
      (node (ref "C14") (pin "1") (pinfunction "1_1") (pintype "passive"))
      (node (ref "R16") (pin "2") (pinfunction "2_2") (pintype "passive"))
    )
    (net (code "23") (name "Net-(C14-Pad2)") (class "Default")
      (node (ref "C14") (pin "2") (pinfunction "2_2") (pintype "passive"))
      (node (ref "C15") (pin "1") (pinfunction "1_1") (pintype "passive"))
      (node (ref "R17") (pin "1") (pinfunction "1_1") (pintype "passive"))
    )
    (net (code "24") (name "Net-(C27-Pad1)") (class "Default")
      (node (ref "C27") (pin "1") (pinfunction "1_1") (pintype "passive"))
      (node (ref "D12") (pin "A") (pinfunction "A_A") (pintype "passive"))
    )
    (net (code "25") (name "Net-(C29-Pad1)") (class "Default")
      (node (ref "C29") (pin "1") (pinfunction "1_1") (pintype "passive"))
      (node (ref "D13") (pin "A") (pinfunction "A_A") (pintype "passive"))
    )
    (net (code "26") (name "Net-(C31-Pad1)") (class "Default")
      (node (ref "C31") (pin "1") (pinfunction "1_1") (pintype "passive"))
      (node (ref "D14") (pin "A") (pinfunction "A_A") (pintype "passive"))
    )
    (net (code "27") (name "Net-(D9-PadA)") (class "Default")
      (node (ref "D9") (pin "A") (pinfunction "A_A") (pintype "passive"))
      (node (ref "R21") (pin "1") (pinfunction "1_1") (pintype "passive"))
    )
    (net (code "28") (name "Net-(D10-PadC)") (class "Default")
      (node (ref "D10") (pin "C") (pinfunction "C_C") (pintype "passive"))
      (node (ref "R22") (pin "2") (pinfunction "2_2") (pintype "passive"))
    )
    (net (code "29") (name "Net-(D11-PadA)") (class "Default")
      (node (ref "D11") (pin "A") (pinfunction "A_A") (pintype "passive"))
      (node (ref "R25") (pin "1") (pinfunction "1_1") (pintype "passive"))
    )
    (net (code "30") (name "Net-(Q1-G)") (class "Default")
      (node (ref "Q1") (pin "1") (pinfunction "G_1") (pintype "bidirectional"))
      (node (ref "Q2") (pin "3") (pinfunction "D_3") (pintype "bidirectional"))
      (node (ref "R33") (pin "1") (pinfunction "1_1") (pintype "passive"))
    )
    (net (code "31") (name "Net-(Q2-G)") (class "Default")
      (node (ref "Q2") (pin "1") (pinfunction "G_1") (pintype "bidirectional"))
      (node (ref "U6") (pin "6") (pinfunction "OUT_6") (pintype "output"))
    )
    (net (code "32") (name "Net-(Q3-G)") (class "Default")
      (node (ref "Q3") (pin "1") (pinfunction "G_1") (pintype "bidirectional"))
      (node (ref "Q4") (pin "3") (pinfunction "D_3") (pintype "bidirectional"))
      (node (ref "R38") (pin "1") (pinfunction "1_1") (pintype "passive"))
    )
    (net (code "33") (name "Net-(Q4-G)") (class "Default")
      (node (ref "Q4") (pin "1") (pinfunction "G_1") (pintype "bidirectional"))
      (node (ref "U7") (pin "6") (pinfunction "OUT_6") (pintype "output"))
    )
    (net (code "34") (name "Net-(Q5-G)") (class "Default")
      (node (ref "Q5") (pin "1") (pinfunction "G_1") (pintype "bidirectional"))
      (node (ref "Q6") (pin "3") (pinfunction "D_3") (pintype "bidirectional"))
      (node (ref "R43") (pin "1") (pinfunction "1_1") (pintype "passive"))
    )
    (net (code "35") (name "Net-(Q6-G)") (class "Default")
      (node (ref "Q6") (pin "1") (pinfunction "G_1") (pintype "bidirectional"))
      (node (ref "U8") (pin "6") (pinfunction "OUT_6") (pintype "output"))
    )
    (net (code "36") (name "Net-(RT1-Pad2)") (class "Default")
      (node (ref "RT1") (pin "2") (pinfunction "2_2") (pintype "passive"))
      (node (ref "TR1") (pin "1") (pinfunction "1_1") (pintype "passive"))
    )
    (net (code "37") (name "Net-(S1-O)") (class "Default")
      (node (ref "RT1") (pin "1") (pinfunction "1_1") (pintype "passive"))
      (node (ref "S1") (pin "1") (pinfunction "O_1") (pintype "passive"))
    )
    (net (code "38") (name "Net-(S1-P)") (class "Default")
      (node (ref "S1") (pin "2") (pinfunction "P_2") (pintype "passive"))
      (node (ref "U$18") (pin "2") (pinfunction "P$2_2") (pintype "bidirectional"))
    )
    (net (code "39") (name "Net-(TR1-3)") (class "Default")
      (node (ref "D3") (pin "C") (pinfunction "C_C") (pintype "passive"))
      (node (ref "D4") (pin "A") (pinfunction "A_A") (pintype "passive"))
      (node (ref "TR1") (pin "5") (pinfunction "3_5") (pintype "passive"))
    )
    (net (code "40") (name "Net-(TR1-6)") (class "Default")
      (node (ref "D1") (pin "C") (pinfunction "C_C") (pintype "passive"))
      (node (ref "D2") (pin "A") (pinfunction "A_A") (pintype "passive"))
      (node (ref "TR1") (pin "8") (pinfunction "6_8") (pintype "passive"))
    )
    (net (code "41") (name "Net-(U1A-+IN)") (class "Default")
      (node (ref "C1") (pin "2") (pinfunction "2_2") (pintype "passive"))
      (node (ref "U1") (pin "3") (pinfunction "+IN_3") (pintype "input"))
    )
    (net (code "42") (name "Net-(U1B-+IN)") (class "Default")
      (node (ref "C4") (pin "1") (pinfunction "1_1") (pintype "passive"))
      (node (ref "R3") (pin "2") (pinfunction "2_2") (pintype "passive"))
      (node (ref "U1") (pin "5") (pinfunction "+IN_5") (pintype "input"))
    )
    (net (code "43") (name "Net-(U1B--IN)") (class "Default")
      (node (ref "C3") (pin "1") (pinfunction "1_1") (pintype "passive"))
      (node (ref "C5") (pin "2") (pinfunction "2_2") (pintype "passive"))
      (node (ref "U1") (pin "6") (pinfunction "-IN_6") (pintype "input"))
      (node (ref "U1") (pin "7") (pinfunction "OUT_7") (pintype "output"))
    )
    (net (code "44") (name "Net-(U1C-+IN)") (class "Default")
      (node (ref "C5") (pin "1") (pinfunction "1_1") (pintype "passive"))
      (node (ref "U1") (pin "10") (pinfunction "+IN_10") (pintype "input"))
    )
    (net (code "45") (name "Net-(U1C--IN)") (class "Default")
      (node (ref "R6") (pin "2") (pinfunction "2_2") (pintype "passive"))
      (node (ref "R7") (pin "1") (pinfunction "1_1") (pintype "passive"))
      (node (ref "U1") (pin "9") (pinfunction "-IN_9") (pintype "input"))
    )
    (net (code "46") (name "Net-(U1C-OUT)") (class "Default")
      (node (ref "C27") (pin "2") (pinfunction "2_2") (pintype "passive"))
      (node (ref "R7") (pin "2") (pinfunction "2_2") (pintype "passive"))
      (node (ref "U1") (pin "8") (pinfunction "OUT_8") (pintype "output"))
    )
    (net (code "47") (name "Net-(U1D-+IN)") (class "Default")
      (node (ref "C28") (pin "1") (pinfunction "1_1") (pintype "passive"))
      (node (ref "D12") (pin "C") (pinfunction "C_C") (pintype "passive"))
      (node (ref "R26") (pin "2") (pinfunction "2_2") (pintype "passive"))
      (node (ref "U1") (pin "12") (pinfunction "+IN_12") (pintype "input"))
    )
    (net (code "48") (name "Net-(U2A-+IN)") (class "Default")
      (node (ref "C8") (pin "1") (pinfunction "1_1") (pintype "passive"))
      (node (ref "R10") (pin "2") (pinfunction "2_2") (pintype "passive"))
      (node (ref "U2") (pin "3") (pinfunction "+IN_3") (pintype "input"))
    )
    (net (code "49") (name "Net-(U2A--IN)") (class "Default")
      (node (ref "C7") (pin "1") (pinfunction "1_1") (pintype "passive"))
      (node (ref "C9") (pin "1") (pinfunction "1_1") (pintype "passive"))
      (node (ref "U2") (pin "1") (pinfunction "OUT_1") (pintype "output"))
      (node (ref "U2") (pin "2") (pinfunction "-IN_2") (pintype "input"))
    )
    (net (code "50") (name "Net-(U2B-+IN)") (class "Default")
      (node (ref "C11") (pin "2") (pinfunction "2_2") (pintype "passive"))
      (node (ref "R13") (pin "2") (pinfunction "2_2") (pintype "passive"))
      (node (ref "U2") (pin "5") (pinfunction "+IN_5") (pintype "input"))
    )
    (net (code "51") (name "Net-(U2B--IN)") (class "Default")
      (node (ref "C12") (pin "2") (pinfunction "2_2") (pintype "passive"))
      (node (ref "R12") (pin "2") (pinfunction "2_2") (pintype "passive"))
      (node (ref "U2") (pin "6") (pinfunction "-IN_6") (pintype "input"))
      (node (ref "U2") (pin "7") (pinfunction "OUT_7") (pintype "output"))
    )
    (net (code "52") (name "Net-(U2C-+IN)") (class "Default")
      (node (ref "C12") (pin "1") (pinfunction "1_1") (pintype "passive"))
      (node (ref "U2") (pin "10") (pinfunction "+IN_10") (pintype "input"))
    )
    (net (code "53") (name "Net-(U2C--IN)") (class "Default")
      (node (ref "R14") (pin "2") (pinfunction "2_2") (pintype "passive"))
      (node (ref "R15") (pin "1") (pinfunction "1_1") (pintype "passive"))
      (node (ref "U2") (pin "9") (pinfunction "-IN_9") (pintype "input"))
    )
    (net (code "54") (name "Net-(U2C-OUT)") (class "Default")
      (node (ref "C29") (pin "2") (pinfunction "2_2") (pintype "passive"))
      (node (ref "R15") (pin "2") (pinfunction "2_2") (pintype "passive"))
      (node (ref "U2") (pin "8") (pinfunction "OUT_8") (pintype "output"))
    )
    (net (code "55") (name "Net-(U2D-+IN)") (class "Default")
      (node (ref "C30") (pin "1") (pinfunction "1_1") (pintype "passive"))
      (node (ref "D13") (pin "C") (pinfunction "C_C") (pintype "passive"))
      (node (ref "R27") (pin "2") (pinfunction "2_2") (pintype "passive"))
      (node (ref "U2") (pin "12") (pinfunction "+IN_12") (pintype "input"))
    )
    (net (code "56") (name "Net-(U3A-+IN)") (class "Default")
      (node (ref "C15") (pin "2") (pinfunction "2_2") (pintype "passive"))
      (node (ref "R18") (pin "2") (pinfunction "2_2") (pintype "passive"))
      (node (ref "U3") (pin "3") (pinfunction "+IN_3") (pintype "input"))
    )
    (net (code "57") (name "Net-(U3A--IN)") (class "Default")
      (node (ref "C16") (pin "2") (pinfunction "2_2") (pintype "passive"))
      (node (ref "R17") (pin "2") (pinfunction "2_2") (pintype "passive"))
      (node (ref "U3") (pin "1") (pinfunction "OUT_1") (pintype "output"))
      (node (ref "U3") (pin "2") (pinfunction "-IN_2") (pintype "input"))
    )
    (net (code "58") (name "Net-(U3B-+IN)") (class "Default")
      (node (ref "C16") (pin "1") (pinfunction "1_1") (pintype "passive"))
      (node (ref "U3") (pin "5") (pinfunction "+IN_5") (pintype "input"))
    )
    (net (code "59") (name "Net-(U3B--IN)") (class "Default")
      (node (ref "R19") (pin "1") (pinfunction "1_1") (pintype "passive"))
      (node (ref "R20") (pin "2") (pinfunction "2_2") (pintype "passive"))
      (node (ref "U3") (pin "6") (pinfunction "-IN_6") (pintype "input"))
    )
    (net (code "60") (name "Net-(U3B-OUT)") (class "Default")
      (node (ref "C31") (pin "2") (pinfunction "2_2") (pintype "passive"))
      (node (ref "R19") (pin "2") (pinfunction "2_2") (pintype "passive"))
      (node (ref "U3") (pin "7") (pinfunction "OUT_7") (pintype "output"))
    )
    (net (code "61") (name "Net-(U3C-+IN)") (class "Default")
      (node (ref "C32") (pin "1") (pinfunction "1_1") (pintype "passive"))
      (node (ref "D14") (pin "C") (pinfunction "C_C") (pintype "passive"))
      (node (ref "R28") (pin "2") (pinfunction "2_2") (pintype "passive"))
      (node (ref "U3") (pin "10") (pinfunction "+IN_10") (pintype "input"))
    )
    (net (code "62") (name "Net-(U6-DIV)") (class "Default")
      (node (ref "R30") (pin "2") (pinfunction "2_2") (pintype "passive"))
      (node (ref "R31") (pin "2") (pinfunction "2_2") (pintype "passive"))
      (node (ref "U6") (pin "4") (pinfunction "DIV_4") (pintype "input"))
    )
    (net (code "63") (name "Net-(U6-MOD)") (class "Default")
      (node (ref "C33") (pin "1") (pinfunction "1_1") (pintype "passive"))
      (node (ref "U6") (pin "1") (pinfunction "MOD_1") (pintype "input"))
      (node (ref "VR2") (pin "2") (pinfunction "WIPER_2") (pintype "passive"))
    )
    (net (code "64") (name "Net-(U6-SET)") (class "Default")
      (node (ref "R29") (pin "2") (pinfunction "2_2") (pintype "passive"))
      (node (ref "U6") (pin "3") (pinfunction "SET_3") (pintype "input"))
    )
    (net (code "65") (name "Net-(U7-DIV)") (class "Default")
      (node (ref "R35") (pin "2") (pinfunction "2_2") (pintype "passive"))
      (node (ref "R36") (pin "2") (pinfunction "2_2") (pintype "passive"))
      (node (ref "U7") (pin "4") (pinfunction "DIV_4") (pintype "input"))
    )
    (net (code "66") (name "Net-(U7-MOD)") (class "Default")
      (node (ref "C35") (pin "1") (pinfunction "1_1") (pintype "passive"))
      (node (ref "U7") (pin "1") (pinfunction "MOD_1") (pintype "input"))
      (node (ref "VR4") (pin "2") (pinfunction "WIPER_2") (pintype "passive"))
    )
    (net (code "67") (name "Net-(U7-SET)") (class "Default")
      (node (ref "R34") (pin "2") (pinfunction "2_2") (pintype "passive"))
      (node (ref "U7") (pin "3") (pinfunction "SET_3") (pintype "input"))
    )
    (net (code "68") (name "Net-(U8-DIV)") (class "Default")
      (node (ref "R40") (pin "2") (pinfunction "2_2") (pintype "passive"))
      (node (ref "R41") (pin "2") (pinfunction "2_2") (pintype "passive"))
      (node (ref "U8") (pin "4") (pinfunction "DIV_4") (pintype "input"))
    )
    (net (code "69") (name "Net-(U8-MOD)") (class "Default")
      (node (ref "C37") (pin "1") (pinfunction "1_1") (pintype "passive"))
      (node (ref "U8") (pin "1") (pinfunction "MOD_1") (pintype "input"))
      (node (ref "VR6") (pin "2") (pinfunction "WIPER_2") (pintype "passive"))
    )
    (net (code "70") (name "Net-(U8-SET)") (class "Default")
      (node (ref "R39") (pin "2") (pinfunction "2_2") (pintype "passive"))
      (node (ref "U8") (pin "3") (pinfunction "SET_3") (pintype "input"))
    )
    (net (code "71") (name "Net-(VR1-CCW)") (class "Default")
      (node (ref "R32") (pin "1") (pinfunction "1_1") (pintype "passive"))
      (node (ref "VR1") (pin "1") (pinfunction "CCW_1") (pintype "passive"))
    )
    (net (code "72") (name "Net-(VR1-WIPER)") (class "Default")
      (node (ref "C33") (pin "2") (pinfunction "2_2") (pintype "passive"))
      (node (ref "VR1") (pin "2") (pinfunction "WIPER_2") (pintype "passive"))
    )
    (net (code "73") (name "Net-(VR3-CCW)") (class "Default")
      (node (ref "R37") (pin "1") (pinfunction "1_1") (pintype "passive"))
      (node (ref "VR3") (pin "1") (pinfunction "CCW_1") (pintype "passive"))
    )
    (net (code "74") (name "Net-(VR3-WIPER)") (class "Default")
      (node (ref "C35") (pin "2") (pinfunction "2_2") (pintype "passive"))
      (node (ref "VR3") (pin "2") (pinfunction "WIPER_2") (pintype "passive"))
    )
    (net (code "75") (name "Net-(VR5-CCW)") (class "Default")
      (node (ref "R42") (pin "1") (pinfunction "1_1") (pintype "passive"))
      (node (ref "VR5") (pin "1") (pinfunction "CCW_1") (pintype "passive"))
    )
    (net (code "76") (name "Net-(VR5-WIPER)") (class "Default")
      (node (ref "C37") (pin "2") (pinfunction "2_2") (pintype "passive"))
      (node (ref "VR5") (pin "2") (pinfunction "WIPER_2") (pintype "passive"))
    )
    (net (code "77") (name "RED") (class "Default")
      (node (ref "J2") (pin "1") (pinfunction "1_1") (pintype "passive"))
      (node (ref "Q5") (pin "2") (pinfunction "S_2") (pintype "bidirectional"))
    )
    (net (code "78") (name "RIGHT_IN") (class "Default")
      (node (ref "J1") (pin "TIP") (pinfunction "TIP_TIP") (pintype "bidirectional"))
      (node (ref "R2") (pin "1") (pinfunction "1_1") (pintype "passive"))
    )
    (net (code "79") (name "V+") (class "Default")
      (node (ref "C17") (pin "+") (pinfunction "+_+") (pintype "passive"))
      (node (ref "C20") (pin "+") (pinfunction "+_+") (pintype "passive"))
      (node (ref "D2") (pin "C") (pinfunction "C_C") (pintype "passive"))
      (node (ref "D4") (pin "C") (pinfunction "C_C") (pintype "passive"))
      (node (ref "D5") (pin "C") (pinfunction "C_C") (pintype "passive"))
      (node (ref "Q1") (pin "3") (pinfunction "D_3") (pintype "bidirectional"))
      (node (ref "Q3") (pin "3") (pinfunction "D_3") (pintype "bidirectional"))
      (node (ref "Q5") (pin "3") (pinfunction "D_3") (pintype "bidirectional"))
      (node (ref "R23") (pin "P$2") (pinfunction "2_P$2") (pintype "passive"))
      (node (ref "R25") (pin "2") (pinfunction "2_2") (pintype "passive"))
      (node (ref "R33") (pin "2") (pinfunction "2_2") (pintype "passive"))
      (node (ref "R38") (pin "2") (pinfunction "2_2") (pintype "passive"))
      (node (ref "R43") (pin "2") (pinfunction "2_2") (pintype "passive"))
      (node (ref "U4") (pin "1") (pinfunction "IN_1") (pintype "input"))
    )
    (net (code "80") (name "V-") (class "Default")
      (node (ref "C18") (pin "-") (pinfunction "-_-") (pintype "passive"))
      (node (ref "C19") (pin "-") (pinfunction "-_-") (pintype "passive"))
      (node (ref "D1") (pin "A") (pinfunction "A_A") (pintype "passive"))
      (node (ref "D11") (pin "C") (pinfunction "C_C") (pintype "passive"))
      (node (ref "D3") (pin "A") (pinfunction "A_A") (pintype "passive"))
      (node (ref "D8") (pin "A") (pinfunction "A_A") (pintype "passive"))
      (node (ref "J2") (pin "4") (pinfunction "4_4") (pintype "passive"))
      (node (ref "R24") (pin "P$1") (pinfunction "1_P$1") (pintype "passive"))
      (node (ref "U5") (pin "1") (pinfunction "IN_1") (pintype "input"))
    )
    (net (code "81") (name "VCC") (class "Default")
      (node (ref "C21") (pin "1") (pinfunction "1_1") (pintype "passive"))
      (node (ref "C23") (pin "1") (pinfunction "1_1") (pintype "passive"))
      (node (ref "C25") (pin "1") (pinfunction "1_1") (pintype "passive"))
      (node (ref "C34") (pin "1") (pinfunction "1_1") (pintype "passive"))
      (node (ref "C36") (pin "1") (pinfunction "1_1") (pintype "passive"))
      (node (ref "C38") (pin "1") (pinfunction "1_1") (pintype "passive"))
      (node (ref "D5") (pin "A") (pinfunction "A_A") (pintype "passive"))
      (node (ref "D6") (pin "C") (pinfunction "C_C") (pintype "passive"))
      (node (ref "R21") (pin "2") (pinfunction "2_2") (pintype "passive"))
      (node (ref "R31") (pin "1") (pinfunction "1_1") (pintype "passive"))
      (node (ref "R36") (pin "1") (pinfunction "1_1") (pintype "passive"))
      (node (ref "R41") (pin "1") (pinfunction "1_1") (pintype "passive"))
      (node (ref "U1") (pin "4") (pinfunction "P$V+_4") (pintype "bidirectional"))
      (node (ref "U2") (pin "4") (pinfunction "P$V+_4") (pintype "bidirectional"))
      (node (ref "U3") (pin "4") (pinfunction "P$V+_4") (pintype "bidirectional"))
      (node (ref "U4") (pin "2") (pinfunction "OUT_2") (pintype "passive"))
      (node (ref "U6") (pin "5") (pinfunction "V+_5") (pintype "power_in"))
      (node (ref "U7") (pin "5") (pinfunction "V+_5") (pintype "power_in"))
      (node (ref "U8") (pin "5") (pinfunction "V+_5") (pintype "power_in"))
      (node (ref "VR2") (pin "1") (pinfunction "CCW_1") (pintype "passive"))
      (node (ref "VR4") (pin "1") (pinfunction "CCW_1") (pintype "passive"))
      (node (ref "VR6") (pin "1") (pinfunction "CCW_1") (pintype "passive"))
    )
    (net (code "82") (name "VEE") (class "Default")
      (node (ref "C22") (pin "2") (pinfunction "2_2") (pintype "passive"))
      (node (ref "C24") (pin "2") (pinfunction "2_2") (pintype "passive"))
      (node (ref "C26") (pin "2") (pinfunction "2_2") (pintype "passive"))
      (node (ref "D7") (pin "A") (pinfunction "A_A") (pintype "passive"))
      (node (ref "D8") (pin "C") (pinfunction "C_C") (pintype "passive"))
      (node (ref "R22") (pin "1") (pinfunction "1_1") (pintype "passive"))
      (node (ref "U1") (pin "11") (pinfunction "P$V-_11") (pintype "bidirectional"))
      (node (ref "U2") (pin "11") (pinfunction "P$V-_11") (pintype "bidirectional"))
      (node (ref "U3") (pin "11") (pinfunction "P$V-_11") (pintype "bidirectional"))
      (node (ref "U5") (pin "2") (pinfunction "OUT_2") (pintype "passive"))
    )
    (net (code "83") (name "unconnected-(J1-PadRSH)") (class "Default")
      (node (ref "J1") (pin "RSH") (pinfunction "RSH_RSH") (pintype "bidirectional"))
    )
    (net (code "84") (name "unconnected-(J1-PadTSH)") (class "Default")
      (node (ref "J1") (pin "TSH") (pinfunction "TSH_TSH") (pintype "bidirectional"))
    )
    (net (code "85") (name "unconnected-(S1-S-Pad3)") (class "Default")
      (node (ref "S1") (pin "3") (pinfunction "S_3") (pintype "passive"))
    )
  )
)
